# 12-MT7688AN_DDR2_I_F-B.net
KiCad netlist of a schematic drawn in Altium Designer
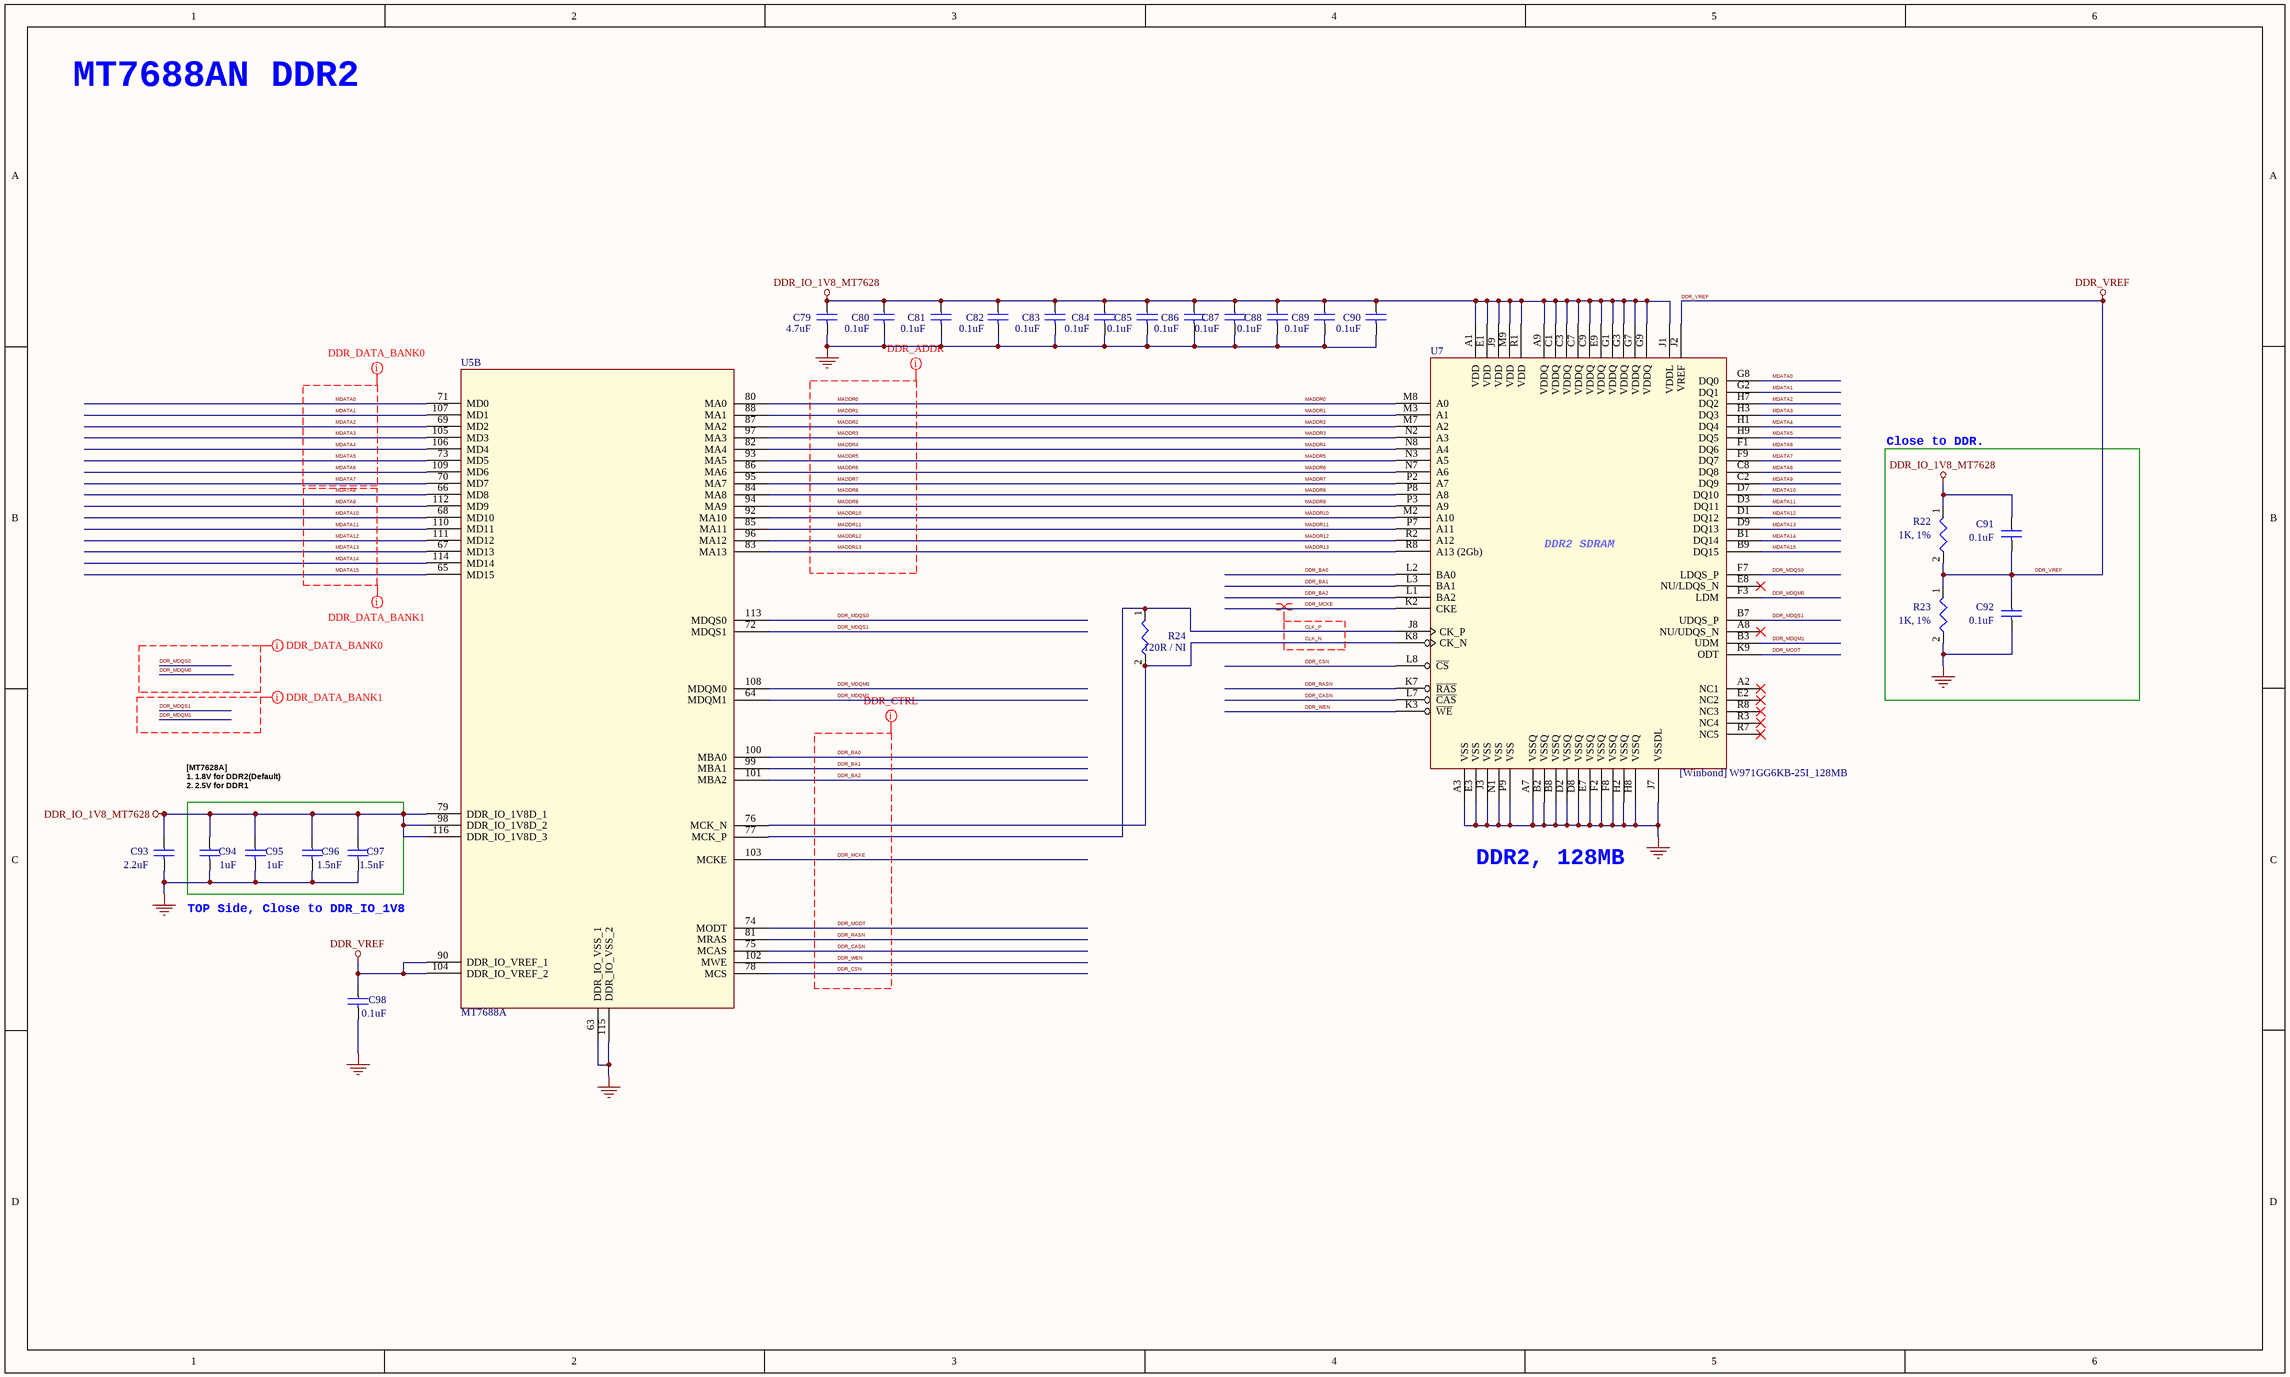
[diagram p0: 12-MT7688AN DDR2 I_F-B.SchDoc]

(export (version "E")
  (design (tool "Eeschema 10.0.6"))
  (components
    (comp (ref "C79")
      (value "4.7uF")
      (footprint "CAPC1608X90X35NL10T15")
      (libsource (lib "MT7688AN") (part "CAP NP"))
    )
    (comp (ref "C80")
      (value "0.1uF")
      (footprint "CAPC1005X60X30NL05T10")
      (libsource (lib "MT7688AN") (part "CAP NP"))
    )
    (comp (ref "C81")
      (value "0.1uF")
      (footprint "CAPC1005X60X30NL05T10")
      (libsource (lib "MT7688AN") (part "CAP NP"))
    )
    (comp (ref "C82")
      (value "0.1uF")
      (footprint "CAPC1005X60X30NL05T10")
      (libsource (lib "MT7688AN") (part "CAP NP"))
    )
    (comp (ref "C83")
      (value "0.1uF")
      (footprint "CAPC1005X60X30NL05T10")
      (libsource (lib "MT7688AN") (part "CAP NP"))
    )
    (comp (ref "C84")
      (value "0.1uF")
      (footprint "CAPC1005X60X30NL05T10")
      (libsource (lib "MT7688AN") (part "CAP NP"))
    )
    (comp (ref "C85")
      (value "0.1uF")
      (footprint "CAPC1005X60X30NL05T10")
      (libsource (lib "MT7688AN") (part "CAP NP"))
    )
    (comp (ref "C86")
      (value "0.1uF")
      (footprint "CAPC1005X60X30NL05T10")
      (libsource (lib "MT7688AN") (part "CAP NP"))
    )
    (comp (ref "C87")
      (value "0.1uF")
      (footprint "CAPC1005X60X30NL05T10")
      (libsource (lib "MT7688AN") (part "CAP NP"))
    )
    (comp (ref "C88")
      (value "0.1uF")
      (footprint "CAPC1005X60X30NL05T10")
      (libsource (lib "MT7688AN") (part "CAP NP"))
    )
    (comp (ref "C89")
      (value "0.1uF")
      (footprint "CAPC1005X60X30NL05T10")
      (libsource (lib "MT7688AN") (part "CAP NP"))
    )
    (comp (ref "C90")
      (value "0.1uF")
      (footprint "CAPC1005X60X30NL05T10")
      (libsource (lib "MT7688AN") (part "CAP NP"))
    )
    (comp (ref "C91")
      (value "0.1uF")
      (footprint "CAPC1005X60X30NL05T10")
      (libsource (lib "MT7688AN") (part "CAP NP"))
    )
    (comp (ref "C92")
      (value "0.1uF")
      (footprint "CAPC1005X60X30NL05T10")
      (libsource (lib "MT7688AN") (part "CAP NP"))
    )
    (comp (ref "C93")
      (value "2.2uF")
      (footprint "CAPC1608X90X35NL10T15")
      (libsource (lib "MT7688AN") (part "CAP NP"))
    )
    (comp (ref "C94")
      (value "1uF")
      (footprint "CAPC1608X90X35NL10T15")
      (libsource (lib "MT7688AN") (part "CAP NP"))
    )
    (comp (ref "C95")
      (value "1uF")
      (footprint "CAPC1608X90X35NL10T15")
      (libsource (lib "MT7688AN") (part "CAP NP"))
    )
    (comp (ref "C96")
      (value "1.5nF")
      (footprint "CAPC1005X60X30NL05T10")
      (libsource (lib "MT7688AN") (part "CAP NP"))
    )
    (comp (ref "C97")
      (value "1.5nF")
      (footprint "CAPC1005X60X30NL05T10")
      (libsource (lib "MT7688AN") (part "CAP NP"))
    )
    (comp (ref "C98")
      (value "0.1uF")
      (footprint "CAPC1005X60X30NL05T10")
      (libsource (lib "MT7688AN") (part "CAP NP"))
    )
    (comp (ref "R22")
      (value "1K, 1%")
      (footprint "RESC1005X35X25NL10T10")
      (libsource (lib "MT7688AN") (part "RES/0402_3"))
    )
    (comp (ref "R23")
      (value "1K, 1%")
      (footprint "RESC1005X35X25NL10T10")
      (libsource (lib "MT7688AN") (part "RES/0402_3"))
    )
    (comp (ref "R24")
      (value "120R / NI")
      (footprint "RLC 0201 M35")
      (libsource (lib "MT7688AN") (part "RES/0402_3"))
    )
    (comp (ref "U5")
      (value "MT7688A")
      (footprint "MT7628AN$2F$DRQFN156$2F$SMD$2F$P0.5$2F$12X12")
      (libsource (lib "MT7688AN") (part "MT7620N-n_26"))
    )
    (comp (ref "U7")
      (value "[Winbond] W971GG6KB-25I_128MB")
      (footprint "BGA84C80P9X15X12X8")
      (description "DDR2, 128MB")
      (libsource (lib "MT7688AN") (part "W971GG6KB-25I"))
    )
  )
  (nets
    (net (code "1") (name "/CLK_N") (class "Default")
      (node (ref "R24") (pin "2") (pinfunction "2_2") (pintype "passive"))
      (node (ref "U5") (pin "76") (pinfunction "MCK_N_76") (pintype "passive"))
      (node (ref "U7") (pin "K8") (pinfunction "CK_N_K8") (pintype "passive"))
    )
    (net (code "2") (name "/CLK_P") (class "Default")
      (node (ref "R24") (pin "1") (pinfunction "1_1") (pintype "passive"))
      (node (ref "U5") (pin "77") (pinfunction "MCK_P_77") (pintype "passive"))
      (node (ref "U7") (pin "J8") (pinfunction "CK_P_J8") (pintype "passive"))
    )
    (net (code "3") (name "/DDR_BA0") (class "Default")
      (node (ref "U5") (pin "100") (pinfunction "MBA0_100") (pintype "passive"))
      (node (ref "U7") (pin "L2") (pinfunction "BA0_L2") (pintype "passive"))
    )
    (net (code "4") (name "/DDR_BA1") (class "Default")
      (node (ref "U5") (pin "99") (pinfunction "MBA1_99") (pintype "passive"))
      (node (ref "U7") (pin "L3") (pinfunction "BA1_L3") (pintype "passive"))
    )
    (net (code "5") (name "/DDR_BA2") (class "Default")
      (node (ref "U5") (pin "101") (pinfunction "MBA2_101") (pintype "passive"))
      (node (ref "U7") (pin "L1") (pinfunction "BA2_L1") (pintype "passive"))
    )
    (net (code "6") (name "/DDR_CASN") (class "Default")
      (node (ref "U5") (pin "75") (pinfunction "MCAS_75") (pintype "passive"))
      (node (ref "U7") (pin "L7") (pinfunction "~{CAS}_L7") (pintype "passive"))
    )
    (net (code "7") (name "/DDR_CSN") (class "Default")
      (node (ref "U5") (pin "78") (pinfunction "MCS_78") (pintype "passive"))
      (node (ref "U7") (pin "L8") (pinfunction "~{CS}_L8") (pintype "passive"))
    )
    (net (code "8") (name "/DDR_MCKE") (class "Default")
      (node (ref "U5") (pin "103") (pinfunction "MCKE_103") (pintype "passive"))
      (node (ref "U7") (pin "K2") (pinfunction "CKE_K2") (pintype "passive"))
    )
    (net (code "9") (name "/DDR_MDQM0") (class "Default")
      (node (ref "U5") (pin "108") (pinfunction "MDQM0_108") (pintype "passive"))
      (node (ref "U7") (pin "F3") (pinfunction "LDM_F3") (pintype "passive"))
    )
    (net (code "10") (name "/DDR_MDQM1") (class "Default")
      (node (ref "U5") (pin "64") (pinfunction "MDQM1_64") (pintype "passive"))
      (node (ref "U7") (pin "B3") (pinfunction "UDM_B3") (pintype "passive"))
    )
    (net (code "11") (name "/DDR_MDQS0") (class "Default")
      (node (ref "U5") (pin "113") (pinfunction "MDQS0_113") (pintype "passive"))
      (node (ref "U7") (pin "F7") (pinfunction "LDQS_P_F7") (pintype "passive"))
    )
    (net (code "12") (name "/DDR_MDQS1") (class "Default")
      (node (ref "U5") (pin "72") (pinfunction "MDQS1_72") (pintype "passive"))
      (node (ref "U7") (pin "B7") (pinfunction "UDQS_P_B7") (pintype "passive"))
    )
    (net (code "13") (name "/DDR_MODT") (class "Default")
      (node (ref "U5") (pin "74") (pinfunction "MODT_74") (pintype "passive"))
      (node (ref "U7") (pin "K9") (pinfunction "ODT_K9") (pintype "passive"))
    )
    (net (code "14") (name "/DDR_RASN") (class "Default")
      (node (ref "U5") (pin "81") (pinfunction "MRAS_81") (pintype "passive"))
      (node (ref "U7") (pin "K7") (pinfunction "~{RAS}_K7") (pintype "passive"))
    )
    (net (code "15") (name "/DDR_WEN") (class "Default")
      (node (ref "U5") (pin "102") (pinfunction "MWE_102") (pintype "passive"))
      (node (ref "U7") (pin "K3") (pinfunction "~{WE}_K3") (pintype "passive"))
    )
    (net (code "16") (name "/MADDR0") (class "Default")
      (node (ref "U5") (pin "80") (pinfunction "MA0_80") (pintype "passive"))
      (node (ref "U7") (pin "M8") (pinfunction "A0_M8") (pintype "passive"))
    )
    (net (code "17") (name "/MADDR1") (class "Default")
      (node (ref "U5") (pin "88") (pinfunction "MA1_88") (pintype "passive"))
      (node (ref "U7") (pin "M3") (pinfunction "A1_M3") (pintype "passive"))
    )
    (net (code "18") (name "/MADDR2") (class "Default")
      (node (ref "U5") (pin "87") (pinfunction "MA2_87") (pintype "passive"))
      (node (ref "U7") (pin "M7") (pinfunction "A2_M7") (pintype "passive"))
    )
    (net (code "19") (name "/MADDR3") (class "Default")
      (node (ref "U5") (pin "97") (pinfunction "MA3_97") (pintype "passive"))
      (node (ref "U7") (pin "N2") (pinfunction "A3_N2") (pintype "passive"))
    )
    (net (code "20") (name "/MADDR4") (class "Default")
      (node (ref "U5") (pin "82") (pinfunction "MA4_82") (pintype "passive"))
      (node (ref "U7") (pin "N8") (pinfunction "A4_N8") (pintype "passive"))
    )
    (net (code "21") (name "/MADDR5") (class "Default")
      (node (ref "U5") (pin "93") (pinfunction "MA5_93") (pintype "passive"))
      (node (ref "U7") (pin "N3") (pinfunction "A5_N3") (pintype "passive"))
    )
    (net (code "22") (name "/MADDR6") (class "Default")
      (node (ref "U5") (pin "86") (pinfunction "MA6_86") (pintype "passive"))
      (node (ref "U7") (pin "N7") (pinfunction "A6_N7") (pintype "passive"))
    )
    (net (code "23") (name "/MADDR7") (class "Default")
      (node (ref "U5") (pin "95") (pinfunction "MA7_95") (pintype "passive"))
      (node (ref "U7") (pin "P2") (pinfunction "A7_P2") (pintype "passive"))
    )
    (net (code "24") (name "/MADDR8") (class "Default")
      (node (ref "U5") (pin "84") (pinfunction "MA8_84") (pintype "passive"))
      (node (ref "U7") (pin "P8") (pinfunction "A8_P8") (pintype "passive"))
    )
    (net (code "25") (name "/MADDR9") (class "Default")
      (node (ref "U5") (pin "94") (pinfunction "MA9_94") (pintype "passive"))
      (node (ref "U7") (pin "P3") (pinfunction "A9_P3") (pintype "passive"))
    )
    (net (code "26") (name "/MADDR10") (class "Default")
      (node (ref "U5") (pin "92") (pinfunction "MA10_92") (pintype "passive"))
      (node (ref "U7") (pin "M2") (pinfunction "A10_M2") (pintype "passive"))
    )
    (net (code "27") (name "/MADDR11") (class "Default")
      (node (ref "U5") (pin "85") (pinfunction "MA11_85") (pintype "passive"))
      (node (ref "U7") (pin "P7") (pinfunction "A11_P7") (pintype "passive"))
    )
    (net (code "28") (name "/MADDR12") (class "Default")
      (node (ref "U5") (pin "96") (pinfunction "MA12_96") (pintype "passive"))
      (node (ref "U7") (pin "R2") (pinfunction "A12_R2") (pintype "passive"))
    )
    (net (code "29") (name "/MADDR13") (class "Default")
      (node (ref "U5") (pin "83") (pinfunction "MA13_83") (pintype "passive"))
      (node (ref "U7") (pin "R8") (pinfunction "A13_(2Gb)_R8") (pintype "passive"))
    )
    (net (code "30") (name "/MDATA0") (class "Default")
      (node (ref "U5") (pin "71") (pinfunction "MD0_71") (pintype "passive"))
      (node (ref "U7") (pin "G8") (pinfunction "DQ0_G8") (pintype "passive"))
    )
    (net (code "31") (name "/MDATA1") (class "Default")
      (node (ref "U5") (pin "107") (pinfunction "MD1_107") (pintype "passive"))
      (node (ref "U7") (pin "G2") (pinfunction "DQ1_G2") (pintype "passive"))
    )
    (net (code "32") (name "/MDATA2") (class "Default")
      (node (ref "U5") (pin "69") (pinfunction "MD2_69") (pintype "passive"))
      (node (ref "U7") (pin "H7") (pinfunction "DQ2_H7") (pintype "passive"))
    )
    (net (code "33") (name "/MDATA3") (class "Default")
      (node (ref "U5") (pin "105") (pinfunction "MD3_105") (pintype "passive"))
      (node (ref "U7") (pin "H3") (pinfunction "DQ3_H3") (pintype "passive"))
    )
    (net (code "34") (name "/MDATA4") (class "Default")
      (node (ref "U5") (pin "106") (pinfunction "MD4_106") (pintype "passive"))
      (node (ref "U7") (pin "H1") (pinfunction "DQ4_H1") (pintype "passive"))
    )
    (net (code "35") (name "/MDATA5") (class "Default")
      (node (ref "U5") (pin "73") (pinfunction "MD5_73") (pintype "passive"))
      (node (ref "U7") (pin "H9") (pinfunction "DQ5_H9") (pintype "passive"))
    )
    (net (code "36") (name "/MDATA6") (class "Default")
      (node (ref "U5") (pin "109") (pinfunction "MD6_109") (pintype "passive"))
      (node (ref "U7") (pin "F1") (pinfunction "DQ6_F1") (pintype "passive"))
    )
    (net (code "37") (name "/MDATA7") (class "Default")
      (node (ref "U5") (pin "70") (pinfunction "MD7_70") (pintype "passive"))
      (node (ref "U7") (pin "F9") (pinfunction "DQ7_F9") (pintype "passive"))
    )
    (net (code "38") (name "/MDATA8") (class "Default")
      (node (ref "U5") (pin "66") (pinfunction "MD8_66") (pintype "passive"))
      (node (ref "U7") (pin "C8") (pinfunction "DQ8_C8") (pintype "passive"))
    )
    (net (code "39") (name "/MDATA9") (class "Default")
      (node (ref "U5") (pin "112") (pinfunction "MD9_112") (pintype "passive"))
      (node (ref "U7") (pin "C2") (pinfunction "DQ9_C2") (pintype "passive"))
    )
    (net (code "40") (name "/MDATA10") (class "Default")
      (node (ref "U5") (pin "68") (pinfunction "MD10_68") (pintype "passive"))
      (node (ref "U7") (pin "D7") (pinfunction "DQ10_D7") (pintype "passive"))
    )
    (net (code "41") (name "/MDATA11") (class "Default")
      (node (ref "U5") (pin "110") (pinfunction "MD11_110") (pintype "passive"))
      (node (ref "U7") (pin "D3") (pinfunction "DQ11_D3") (pintype "passive"))
    )
    (net (code "42") (name "/MDATA12") (class "Default")
      (node (ref "U5") (pin "111") (pinfunction "MD12_111") (pintype "passive"))
      (node (ref "U7") (pin "D1") (pinfunction "DQ12_D1") (pintype "passive"))
    )
    (net (code "43") (name "/MDATA13") (class "Default")
      (node (ref "U5") (pin "67") (pinfunction "MD13_67") (pintype "passive"))
      (node (ref "U7") (pin "D9") (pinfunction "DQ13_D9") (pintype "passive"))
    )
    (net (code "44") (name "/MDATA14") (class "Default")
      (node (ref "U5") (pin "114") (pinfunction "MD14_114") (pintype "passive"))
      (node (ref "U7") (pin "B1") (pinfunction "DQ14_B1") (pintype "passive"))
    )
    (net (code "45") (name "/MDATA15") (class "Default")
      (node (ref "U5") (pin "65") (pinfunction "MD15_65") (pintype "passive"))
      (node (ref "U7") (pin "B9") (pinfunction "DQ15_B9") (pintype "passive"))
    )
    (net (code "46") (name "DDR_IO_1V8_MT7628") (class "Default")
      (node (ref "C79") (pin "1") (pinfunction "1_1") (pintype "passive"))
      (node (ref "C80") (pin "1") (pinfunction "1_1") (pintype "passive"))
      (node (ref "C81") (pin "1") (pinfunction "1_1") (pintype "passive"))
      (node (ref "C82") (pin "1") (pinfunction "1_1") (pintype "passive"))
      (node (ref "C83") (pin "1") (pinfunction "1_1") (pintype "passive"))
      (node (ref "C84") (pin "1") (pinfunction "1_1") (pintype "passive"))
      (node (ref "C85") (pin "1") (pinfunction "1_1") (pintype "passive"))
      (node (ref "C86") (pin "1") (pinfunction "1_1") (pintype "passive"))
      (node (ref "C87") (pin "1") (pinfunction "1_1") (pintype "passive"))
      (node (ref "C88") (pin "1") (pinfunction "1_1") (pintype "passive"))
      (node (ref "C89") (pin "1") (pinfunction "1_1") (pintype "passive"))
      (node (ref "C90") (pin "1") (pinfunction "1_1") (pintype "passive"))
      (node (ref "C91") (pin "1") (pinfunction "1_1") (pintype "passive"))
      (node (ref "C93") (pin "1") (pinfunction "1_1") (pintype "passive"))
      (node (ref "C94") (pin "1") (pinfunction "1_1") (pintype "passive"))
      (node (ref "C95") (pin "1") (pinfunction "1_1") (pintype "passive"))
      (node (ref "C96") (pin "1") (pinfunction "1_1") (pintype "passive"))
      (node (ref "C97") (pin "1") (pinfunction "1_1") (pintype "passive"))
      (node (ref "R22") (pin "1") (pinfunction "1_1") (pintype "passive"))
      (node (ref "U5") (pin "116") (pinfunction "DDR_IO_1V8D_3_116") (pintype "power_in"))
      (node (ref "U5") (pin "79") (pinfunction "DDR_IO_1V8D_1_79") (pintype "power_in"))
      (node (ref "U5") (pin "98") (pinfunction "DDR_IO_1V8D_2_98") (pintype "power_in"))
      (node (ref "U7") (pin "A1") (pinfunction "VDD_A1") (pintype "power_in"))
      (node (ref "U7") (pin "A9") (pinfunction "VDDQ_A9") (pintype "power_in"))
      (node (ref "U7") (pin "C1") (pinfunction "VDDQ_C1") (pintype "power_in"))
      (node (ref "U7") (pin "C3") (pinfunction "VDDQ_C3") (pintype "power_in"))
      (node (ref "U7") (pin "C7") (pinfunction "VDDQ_C7") (pintype "power_in"))
      (node (ref "U7") (pin "C9") (pinfunction "VDDQ_C9") (pintype "power_in"))
      (node (ref "U7") (pin "E1") (pinfunction "VDD_E1") (pintype "power_in"))
      (node (ref "U7") (pin "E9") (pinfunction "VDDQ_E9") (pintype "power_in"))
      (node (ref "U7") (pin "G1") (pinfunction "VDDQ_G1") (pintype "power_in"))
      (node (ref "U7") (pin "G3") (pinfunction "VDDQ_G3") (pintype "power_in"))
      (node (ref "U7") (pin "G7") (pinfunction "VDDQ_G7") (pintype "power_in"))
      (node (ref "U7") (pin "G9") (pinfunction "VDDQ_G9") (pintype "power_in"))
      (node (ref "U7") (pin "J1") (pinfunction "VDDL_J1") (pintype "power_in"))
      (node (ref "U7") (pin "J9") (pinfunction "VDD_J9") (pintype "power_in"))
      (node (ref "U7") (pin "M9") (pinfunction "VDD_M9") (pintype "power_in"))
      (node (ref "U7") (pin "R1") (pinfunction "VDD_R1") (pintype "power_in"))
    )
    (net (code "47") (name "DDR_VREF") (class "Default")
      (node (ref "C91") (pin "2") (pinfunction "2_2") (pintype "passive"))
      (node (ref "C92") (pin "1") (pinfunction "1_1") (pintype "passive"))
      (node (ref "C98") (pin "1") (pinfunction "1_1") (pintype "passive"))
      (node (ref "R22") (pin "2") (pinfunction "2_2") (pintype "passive"))
      (node (ref "R23") (pin "1") (pinfunction "1_1") (pintype "passive"))
      (node (ref "U5") (pin "104") (pinfunction "DDR_IO_VREF_2_104") (pintype "power_in"))
      (node (ref "U5") (pin "90") (pinfunction "DDR_IO_VREF_1_90") (pintype "power_in"))
      (node (ref "U7") (pin "J2") (pinfunction "VREF_J2") (pintype "power_in"))
    )
    (net (code "48") (name "GND") (class "Default")
      (node (ref "C79") (pin "2") (pinfunction "2_2") (pintype "passive"))
      (node (ref "C80") (pin "2") (pinfunction "2_2") (pintype "passive"))
      (node (ref "C81") (pin "2") (pinfunction "2_2") (pintype "passive"))
      (node (ref "C82") (pin "2") (pinfunction "2_2") (pintype "passive"))
      (node (ref "C83") (pin "2") (pinfunction "2_2") (pintype "passive"))
      (node (ref "C84") (pin "2") (pinfunction "2_2") (pintype "passive"))
      (node (ref "C85") (pin "2") (pinfunction "2_2") (pintype "passive"))
      (node (ref "C86") (pin "2") (pinfunction "2_2") (pintype "passive"))
      (node (ref "C87") (pin "2") (pinfunction "2_2") (pintype "passive"))
      (node (ref "C88") (pin "2") (pinfunction "2_2") (pintype "passive"))
      (node (ref "C89") (pin "2") (pinfunction "2_2") (pintype "passive"))
      (node (ref "C90") (pin "2") (pinfunction "2_2") (pintype "passive"))
      (node (ref "C92") (pin "2") (pinfunction "2_2") (pintype "passive"))
      (node (ref "C93") (pin "2") (pinfunction "2_2") (pintype "passive"))
      (node (ref "C94") (pin "2") (pinfunction "2_2") (pintype "passive"))
      (node (ref "C95") (pin "2") (pinfunction "2_2") (pintype "passive"))
      (node (ref "C96") (pin "2") (pinfunction "2_2") (pintype "passive"))
      (node (ref "C97") (pin "2") (pinfunction "2_2") (pintype "passive"))
      (node (ref "C98") (pin "2") (pinfunction "2_2") (pintype "passive"))
      (node (ref "R23") (pin "2") (pinfunction "2_2") (pintype "passive"))
      (node (ref "U5") (pin "115") (pinfunction "DDR_IO_VSS_2_115") (pintype "passive"))
      (node (ref "U5") (pin "63") (pinfunction "DDR_IO_VSS_1_63") (pintype "power_in"))
      (node (ref "U7") (pin "A3") (pinfunction "VSS_A3") (pintype "power_in"))
      (node (ref "U7") (pin "A7") (pinfunction "VSSQ_A7") (pintype "power_in"))
      (node (ref "U7") (pin "B2") (pinfunction "VSSQ_B2") (pintype "power_in"))
      (node (ref "U7") (pin "B8") (pinfunction "VSSQ_B8") (pintype "power_in"))
      (node (ref "U7") (pin "D2") (pinfunction "VSSQ_D2") (pintype "power_in"))
      (node (ref "U7") (pin "D8") (pinfunction "VSSQ_D8") (pintype "power_in"))
      (node (ref "U7") (pin "E3") (pinfunction "VSS_E3") (pintype "power_in"))
      (node (ref "U7") (pin "E7") (pinfunction "VSSQ_E7") (pintype "power_in"))
      (node (ref "U7") (pin "F2") (pinfunction "VSSQ_F2") (pintype "power_in"))
      (node (ref "U7") (pin "F8") (pinfunction "VSSQ_F8") (pintype "power_in"))
      (node (ref "U7") (pin "H2") (pinfunction "VSSQ_H2") (pintype "power_in"))
      (node (ref "U7") (pin "H8") (pinfunction "VSSQ_H8") (pintype "power_in"))
      (node (ref "U7") (pin "J3") (pinfunction "VSS_J3") (pintype "power_in"))
      (node (ref "U7") (pin "J7") (pinfunction "VSSDL_J7") (pintype "power_in"))
      (node (ref "U7") (pin "N1") (pinfunction "VSS_N1") (pintype "power_in"))
      (node (ref "U7") (pin "P9") (pinfunction "VSS_P9") (pintype "power_in"))
    )
    (net (code "49") (name "unconnected-(U7-NC1-PadA2)") (class "Default")
      (node (ref "U7") (pin "A2") (pinfunction "NC1_A2") (pintype "passive+no_connect"))
    )
    (net (code "50") (name "unconnected-(U7-NC2-PadE2)") (class "Default")
      (node (ref "U7") (pin "E2") (pinfunction "NC2_E2") (pintype "passive+no_connect"))
    )
    (net (code "51") (name "unconnected-(U7-NC3-PadR8)") (class "Default")
      (node (ref "U7") (pin "R8") (pinfunction "NC3_R8") (pintype "passive+no_connect"))
    )
    (net (code "52") (name "unconnected-(U7-NC4-PadR3)") (class "Default")
      (node (ref "U7") (pin "R3") (pinfunction "NC4_R3") (pintype "passive+no_connect"))
    )
    (net (code "53") (name "unconnected-(U7-NC5-PadR7)") (class "Default")
      (node (ref "U7") (pin "R7") (pinfunction "NC5_R7") (pintype "passive+no_connect"))
    )
    (net (code "54") (name "unconnected-(U7-NU{slash}LDQS_N-PadE8)") (class "Default")
      (node (ref "U7") (pin "E8") (pinfunction "NU/LDQS_N_E8") (pintype "passive+no_connect"))
    )
    (net (code "55") (name "unconnected-(U7-NU{slash}UDQS_N-PadA8)") (class "Default")
      (node (ref "U7") (pin "A8") (pinfunction "NU/UDQS_N_A8") (pintype "passive+no_connect"))
    )
  )
)
